# RF.net
KiCad netlist of a schematic drawn in Altium Designer
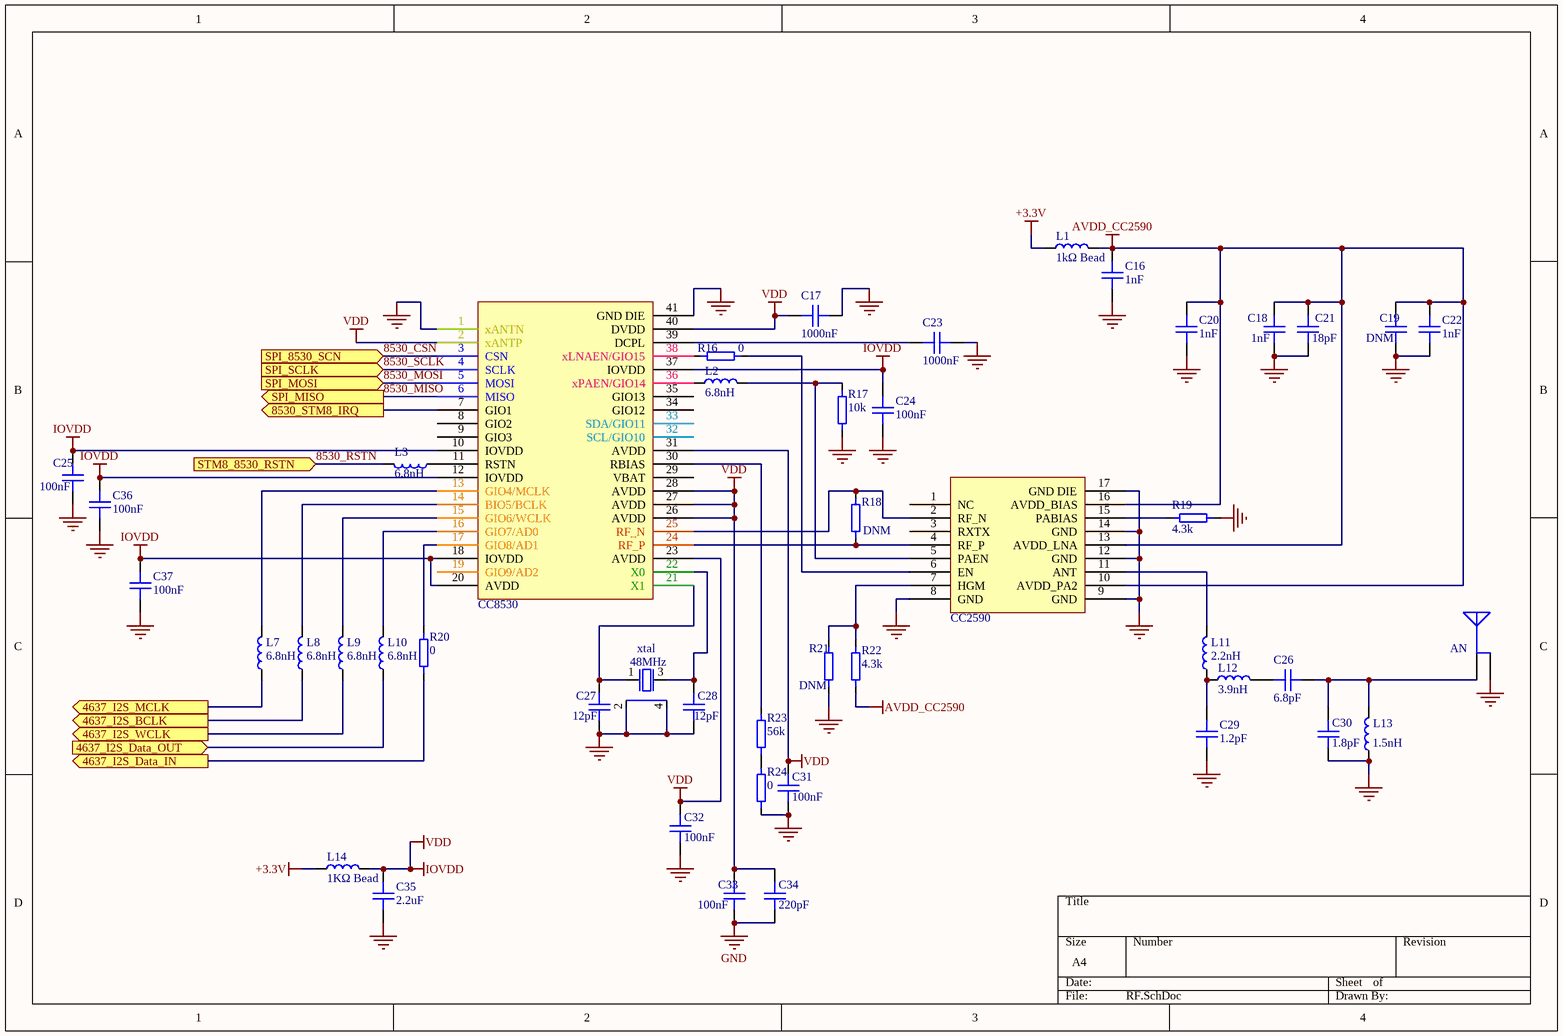
[diagram p0: RF.SchDoc]

(export (version "E")
  (design (tool "Eeschema 10.0.6"))
  (components
    (comp (ref "AN")
      (value "Antenna")
      (footprint "ANT_WIGGLE_1MM")
      (libsource (lib "SuperLib") (part "Antenna"))
    )
    (comp (ref "C16")
      (value "1nF")
      (footprint "SMD 0402")
      (fields (field (name "Comment") "Capacity SMD"))
      (libsource (lib "WPU161C") (part "Capacity SMD"))
    )
    (comp (ref "C17")
      (value "1000nF")
      (footprint "SMD 0402")
      (fields (field (name "Comment") "Capacity SMD"))
      (libsource (lib "WPU161C") (part "Capacity SMD"))
    )
    (comp (ref "C18")
      (value "1nF")
      (footprint "SMD 0402")
      (fields (field (name "Comment") "Capacity SMD"))
      (libsource (lib "WPU161C") (part "Capacity SMD"))
    )
    (comp (ref "C19")
      (value "DNM")
      (footprint "SMD 0402")
      (fields (field (name "Comment") "Capacity SMD"))
      (libsource (lib "WPU161C") (part "Capacity SMD"))
    )
    (comp (ref "C20")
      (value "1nF")
      (footprint "SMD 0402")
      (fields (field (name "Comment") "Capacity SMD"))
      (libsource (lib "WPU161C") (part "Capacity SMD"))
    )
    (comp (ref "C21")
      (value "18pF")
      (footprint "SMD 0402")
      (fields (field (name "Comment") "Capacity SMD"))
      (libsource (lib "WPU161C") (part "Capacity SMD"))
    )
    (comp (ref "C22")
      (value "1nF")
      (footprint "SMD 0402")
      (fields (field (name "Comment") "Capacity SMD"))
      (libsource (lib "WPU161C") (part "Capacity SMD"))
    )
    (comp (ref "C23")
      (value "1000nF")
      (footprint "SMD 0402")
      (fields (field (name "Comment") "Capacity SMD"))
      (libsource (lib "WPU161C") (part "Capacity SMD"))
    )
    (comp (ref "C24")
      (value "100nF")
      (footprint "SMD 0402")
      (fields (field (name "Comment") "Capacity SMD"))
      (libsource (lib "WPU161C") (part "Capacity SMD"))
    )
    (comp (ref "C25")
      (value "100nF")
      (footprint "SMD 0402")
      (fields (field (name "Comment") "Capacity SMD"))
      (libsource (lib "WPU161C") (part "Capacity SMD"))
    )
    (comp (ref "C26")
      (value "6.8pF")
      (footprint "SMD 0402")
      (fields (field (name "Comment") "Capacity SMD"))
      (libsource (lib "WPU161C") (part "Capacity SMD"))
    )
    (comp (ref "C27")
      (value "12pF")
      (footprint "SMD 0402")
      (fields (field (name "Comment") "Capacity SMD"))
      (libsource (lib "WPU161C") (part "Capacity SMD"))
    )
    (comp (ref "C28")
      (value "12pF")
      (footprint "SMD 0402")
      (fields (field (name "Comment") "Capacity SMD"))
      (libsource (lib "WPU161C") (part "Capacity SMD"))
    )
    (comp (ref "C29")
      (value "1.2pF")
      (footprint "SMD 0402")
      (fields (field (name "Comment") "Capacity SMD"))
      (libsource (lib "WPU161C") (part "Capacity SMD"))
    )
    (comp (ref "C30")
      (value "1.8pF")
      (footprint "SMD 0402")
      (fields (field (name "Comment") "Capacity SMD"))
      (libsource (lib "WPU161C") (part "Capacity SMD"))
    )
    (comp (ref "C31")
      (value "100nF")
      (footprint "SMD 0402")
      (fields (field (name "Comment") "Capacity SMD"))
      (libsource (lib "WPU161C") (part "Capacity SMD"))
    )
    (comp (ref "C32")
      (value "100nF")
      (footprint "SMD 0402")
      (fields (field (name "Comment") "Capacity SMD"))
      (libsource (lib "WPU161C") (part "Capacity SMD"))
    )
    (comp (ref "C33")
      (value "100nF")
      (footprint "SMD 0402")
      (fields (field (name "Comment") "Capacity SMD"))
      (libsource (lib "WPU161C") (part "Capacity SMD"))
    )
    (comp (ref "C34")
      (value "220pF")
      (footprint "SMD 0402")
      (fields (field (name "Comment") "Capacity SMD"))
      (libsource (lib "WPU161C") (part "Capacity SMD"))
    )
    (comp (ref "C35")
      (value "2.2uF")
      (footprint "SMD 0402")
      (fields (field (name "Comment") "Capacity SMD"))
      (libsource (lib "WPU161C") (part "Capacity SMD"))
    )
    (comp (ref "C36")
      (value "100nF")
      (footprint "SMD 0402")
      (fields (field (name "Comment") "Capacity SMD"))
      (libsource (lib "WPU161C") (part "Capacity SMD"))
    )
    (comp (ref "C37")
      (value "100nF")
      (footprint "SMD 0402")
      (fields (field (name "Comment") "Capacity SMD"))
      (libsource (lib "WPU161C") (part "Capacity SMD"))
    )
    (comp (ref "CC2590") (value "CC2590") (footprint "CC2590") (libsource (lib "WPU161C") (part "CC2590")))
    (comp (ref "CC8530") (value "CC8530") (footprint "CC8530") (libsource (lib "WPU161C") (part "CC8530")))
    (comp (ref "L1")
      (value "1kΩ Bead")
      (footprint "SMD 0402")
      (fields (field (name "Comment") "Inductor SMD"))
      (libsource (lib "WPU161C") (part "Inductor SMD"))
    )
    (comp (ref "L2")
      (value "6.8nH")
      (footprint "SMD 0402")
      (fields (field (name "Comment") "Inductor SMD"))
      (libsource (lib "WPU161C") (part "Inductor SMD"))
    )
    (comp (ref "L3")
      (value "6.8nH")
      (footprint "SMD 0402")
      (fields (field (name "Comment") "Inductor SMD"))
      (libsource (lib "WPU161C") (part "Inductor SMD"))
    )
    (comp (ref "L7")
      (value "6.8nH")
      (footprint "SMD 0402")
      (fields (field (name "Comment") "Inductor SMD"))
      (libsource (lib "WPU161C") (part "Inductor SMD"))
    )
    (comp (ref "L8")
      (value "6.8nH")
      (footprint "SMD 0402")
      (fields (field (name "Comment") "Inductor SMD"))
      (libsource (lib "WPU161C") (part "Inductor SMD"))
    )
    (comp (ref "L9")
      (value "6.8nH")
      (footprint "SMD 0402")
      (fields (field (name "Comment") "Inductor SMD"))
      (libsource (lib "WPU161C") (part "Inductor SMD"))
    )
    (comp (ref "L10")
      (value "6.8nH")
      (footprint "SMD 0402")
      (fields (field (name "Comment") "Inductor SMD"))
      (libsource (lib "WPU161C") (part "Inductor SMD"))
    )
    (comp (ref "L11")
      (value "2.2nH")
      (footprint "SMD 0402")
      (fields (field (name "Comment") "Inductor SMD"))
      (libsource (lib "WPU161C") (part "Inductor SMD"))
    )
    (comp (ref "L12")
      (value "3.9nH")
      (footprint "SMD 0402")
      (fields (field (name "Comment") "Inductor SMD"))
      (libsource (lib "WPU161C") (part "Inductor SMD"))
    )
    (comp (ref "L13")
      (value "1.5nH")
      (footprint "SMD 0402")
      (fields (field (name "Comment") "Inductor SMD"))
      (libsource (lib "WPU161C") (part "Inductor SMD"))
    )
    (comp (ref "L14")
      (value "1KΩ Bead")
      (footprint "SMD 0402")
      (fields (field (name "Comment") "Inductor SMD"))
      (libsource (lib "WPU161C") (part "Inductor SMD"))
    )
    (comp (ref "R16")
      (value "0")
      (footprint "SMD 0402")
      (fields (field (name "Comment") "Resistor SMD"))
      (libsource (lib "WPU161C") (part "Resistor SMD"))
    )
    (comp (ref "R17")
      (value "10k")
      (footprint "SMD 0402")
      (fields (field (name "Comment") "Resistor SMD"))
      (libsource (lib "WPU161C") (part "Resistor SMD"))
    )
    (comp (ref "R18")
      (value "DNM")
      (footprint "SMD 0402")
      (fields (field (name "Comment") "Resistor SMD"))
      (libsource (lib "WPU161C") (part "Resistor SMD"))
    )
    (comp (ref "R19")
      (value "4.3k")
      (footprint "SMD 0402")
      (fields (field (name "Comment") "Resistor SMD"))
      (libsource (lib "WPU161C") (part "Resistor SMD"))
    )
    (comp (ref "R20")
      (value "0")
      (footprint "SMD 0402")
      (fields (field (name "Comment") "Resistor SMD"))
      (libsource (lib "WPU161C") (part "Resistor SMD"))
    )
    (comp (ref "R21")
      (value "DNM")
      (footprint "SMD 0402")
      (fields (field (name "Comment") "Resistor SMD"))
      (libsource (lib "WPU161C") (part "Resistor SMD"))
    )
    (comp (ref "R22")
      (value "4.3k")
      (footprint "SMD 0402")
      (fields (field (name "Comment") "Resistor SMD"))
      (libsource (lib "WPU161C") (part "Resistor SMD"))
    )
    (comp (ref "R23")
      (value "56k")
      (footprint "SMD 0402")
      (fields (field (name "Comment") "Resistor SMD"))
      (libsource (lib "WPU161C") (part "Resistor SMD"))
    )
    (comp (ref "R24")
      (value "0")
      (footprint "SMD 0402")
      (fields (field (name "Comment") "Resistor SMD"))
      (libsource (lib "WPU161C") (part "Resistor SMD"))
    )
    (comp (ref "xtal")
      (value "48MHz")
      (footprint "xtal_3225_FA-128")
      (fields (field (name "PART NUMBER") "FA-128, 48.00000MHz") (field (name "Comment") "XTAL"))
      (libsource (lib "WPU161C") (part "XTAL"))
    )
  )
  (nets
    (net (code "1") (name "+3.3V") (class "Default")
      (node (ref "L1") (pin "1") (pintype "passive"))
      (node (ref "L14") (pin "1") (pintype "passive"))
    )
    (net (code "2") (name "/4637_I2S_BCLK") (class "Default") (node (ref "L8") (pin "1") (pintype "passive")))
    (net (code "3") (name "/4637_I2S_Data_IN") (class "Default")
      (node (ref "R20") (pin "1") (pintype "passive"))
    )
    (net (code "4") (name "/4637_I2S_Data_OUT") (class "Default")
      (node (ref "L10") (pin "1") (pintype "passive"))
    )
    (net (code "5") (name "/4637_I2S_MCLK") (class "Default") (node (ref "L7") (pin "1") (pintype "passive")))
    (net (code "6") (name "/4637_I2S_WCLK") (class "Default") (node (ref "L9") (pin "1") (pintype "passive")))
    (net (code "7") (name "/8530_CSN") (class "Default")
      (node (ref "CC8530") (pin "3") (pinfunction "CSN_3") (pintype "passive"))
    )
    (net (code "8") (name "/8530_MISO") (class "Default")
      (node (ref "CC8530") (pin "6") (pinfunction "MISO_6") (pintype "passive"))
    )
    (net (code "9") (name "/8530_MOSI") (class "Default")
      (node (ref "CC8530") (pin "5") (pinfunction "MOSI_5") (pintype "passive"))
    )
    (net (code "10") (name "/8530_RSTN") (class "Default") (node (ref "L3") (pin "2") (pintype "passive")))
    (net (code "11") (name "/8530_SCLK") (class "Default")
      (node (ref "CC8530") (pin "4") (pinfunction "SCLK_4") (pintype "passive"))
    )
    (net (code "12") (name "/8530_STM8_IRQ") (class "Default")
      (node (ref "CC8530") (pin "7") (pinfunction "GIO1_7") (pintype "passive"))
    )
    (net (code "13") (name "AVDD_CC2590") (class "Default")
      (node (ref "C16") (pin "2") (pintype "passive"))
      (node (ref "C18") (pin "2") (pintype "passive"))
      (node (ref "C19") (pin "2") (pintype "passive"))
      (node (ref "C20") (pin "2") (pintype "passive"))
      (node (ref "C21") (pin "2") (pintype "passive"))
      (node (ref "C22") (pin "2") (pintype "passive"))
      (node (ref "CC2590") (pin "10") (pinfunction "AVDD_PA2_10") (pintype "passive"))
      (node (ref "CC2590") (pin "13") (pinfunction "AVDD_LNA_13") (pintype "passive"))
      (node (ref "CC2590") (pin "16") (pinfunction "AVDD_BIAS_16") (pintype "passive"))
      (node (ref "L1") (pin "2") (pintype "passive"))
      (node (ref "R22") (pin "1") (pintype "passive"))
    )
    (net (code "14") (name "GND") (class "Default")
      (node (ref "AN") (pin "2") (pintype "passive"))
      (node (ref "C16") (pin "1") (pintype "passive"))
      (node (ref "C17") (pin "2") (pintype "passive"))
      (node (ref "C18") (pin "1") (pintype "passive"))
      (node (ref "C19") (pin "1") (pintype "passive"))
      (node (ref "C20") (pin "1") (pintype "passive"))
      (node (ref "C21") (pin "1") (pintype "passive"))
      (node (ref "C22") (pin "1") (pintype "passive"))
      (node (ref "C23") (pin "2") (pintype "passive"))
      (node (ref "C24") (pin "1") (pintype "passive"))
      (node (ref "C25") (pin "1") (pintype "passive"))
      (node (ref "C27") (pin "1") (pintype "passive"))
      (node (ref "C28") (pin "1") (pintype "passive"))
      (node (ref "C29") (pin "1") (pintype "passive"))
      (node (ref "C30") (pin "1") (pintype "passive"))
      (node (ref "C31") (pin "1") (pintype "passive"))
      (node (ref "C32") (pin "1") (pintype "passive"))
      (node (ref "C33") (pin "1") (pintype "passive"))
      (node (ref "C34") (pin "1") (pintype "passive"))
      (node (ref "C35") (pin "1") (pintype "passive"))
      (node (ref "C36") (pin "1") (pintype "passive"))
      (node (ref "C37") (pin "1") (pintype "passive"))
      (node (ref "CC2590") (pin "12") (pinfunction "GND_12") (pintype "passive"))
      (node (ref "CC2590") (pin "14") (pinfunction "GND_14") (pintype "passive"))
      (node (ref "CC2590") (pin "17") (pinfunction "GND_DIE_17") (pintype "passive"))
      (node (ref "CC2590") (pin "8") (pinfunction "GND_8") (pintype "passive"))
      (node (ref "CC2590") (pin "9") (pinfunction "GND_9") (pintype "passive"))
      (node (ref "CC8530") (pin "1") (pinfunction "xANTN_1") (pintype "passive"))
      (node (ref "CC8530") (pin "41") (pinfunction "GND_DIE_41") (pintype "passive"))
      (node (ref "L13") (pin "1") (pintype "passive"))
      (node (ref "R17") (pin "1") (pintype "passive"))
      (node (ref "R19") (pin "2") (pintype "passive"))
      (node (ref "R21") (pin "1") (pintype "passive"))
      (node (ref "R24") (pin "1") (pintype "passive"))
      (node (ref "xtal") (pin "2") (pinfunction "2_2") (pintype "passive"))
      (node (ref "xtal") (pin "4") (pinfunction "4_4") (pintype "passive"))
    )
    (net (code "15") (name "IOVDD") (class "Default")
      (node (ref "C17") (pin "1") (pintype "passive"))
      (node (ref "C24") (pin "2") (pintype "passive"))
      (node (ref "C25") (pin "2") (pintype "passive"))
      (node (ref "C31") (pin "2") (pintype "passive"))
      (node (ref "C32") (pin "2") (pintype "passive"))
      (node (ref "C33") (pin "2") (pintype "passive"))
      (node (ref "C34") (pin "2") (pintype "passive"))
      (node (ref "C35") (pin "2") (pintype "passive"))
      (node (ref "C36") (pin "2") (pintype "passive"))
      (node (ref "C37") (pin "2") (pintype "passive"))
      (node (ref "CC8530") (pin "10") (pinfunction "IOVDD_10") (pintype "passive"))
      (node (ref "CC8530") (pin "12") (pinfunction "IOVDD_12") (pintype "passive"))
      (node (ref "CC8530") (pin "18") (pinfunction "IOVDD_18") (pintype "passive"))
      (node (ref "CC8530") (pin "2") (pinfunction "xANTP_2") (pintype "passive"))
      (node (ref "CC8530") (pin "20") (pinfunction "AVDD_20") (pintype "passive"))
      (node (ref "CC8530") (pin "23") (pinfunction "AVDD_23") (pintype "passive"))
      (node (ref "CC8530") (pin "26") (pinfunction "AVDD_26") (pintype "passive"))
      (node (ref "CC8530") (pin "27") (pinfunction "AVDD_27") (pintype "passive"))
      (node (ref "CC8530") (pin "28") (pinfunction "AVDD_28") (pintype "passive"))
      (node (ref "CC8530") (pin "31") (pinfunction "AVDD_31") (pintype "passive"))
      (node (ref "CC8530") (pin "37") (pinfunction "IOVDD_37") (pintype "passive"))
      (node (ref "CC8530") (pin "40") (pinfunction "DVDD_40") (pintype "passive"))
      (node (ref "L14") (pin "2") (pintype "passive"))
    )
    (net (code "16") (name "Net-(AN-Pad1)") (class "Default")
      (node (ref "AN") (pin "1") (pintype "passive"))
      (node (ref "C26") (pin "2") (pintype "passive"))
      (node (ref "C30") (pin "2") (pintype "passive"))
      (node (ref "L13") (pin "2") (pintype "passive"))
    )
    (net (code "17") (name "Net-(C26-Pad1)") (class "Default")
      (node (ref "C26") (pin "1") (pintype "passive"))
      (node (ref "L12") (pin "2") (pintype "passive"))
    )
    (net (code "18") (name "Net-(C29-Pad2)") (class "Default")
      (node (ref "C29") (pin "2") (pintype "passive"))
      (node (ref "L11") (pin "1") (pintype "passive"))
      (node (ref "L12") (pin "1") (pintype "passive"))
    )
    (net (code "19") (name "Net-(CC2590-ANT)") (class "Default")
      (node (ref "CC2590") (pin "11") (pinfunction "ANT_11") (pintype "passive"))
      (node (ref "L11") (pin "2") (pintype "passive"))
    )
    (net (code "20") (name "Net-(CC2590-EN)") (class "Default")
      (node (ref "CC2590") (pin "6") (pinfunction "EN_6") (pintype "passive"))
      (node (ref "R16") (pin "2") (pintype "passive"))
    )
    (net (code "21") (name "Net-(CC2590-HGM)") (class "Default")
      (node (ref "CC2590") (pin "7") (pinfunction "HGM_7") (pintype "passive"))
      (node (ref "R21") (pin "2") (pintype "passive"))
      (node (ref "R22") (pin "2") (pintype "passive"))
    )
    (net (code "22") (name "Net-(CC2590-PABIAS)") (class "Default")
      (node (ref "CC2590") (pin "15") (pinfunction "PABIAS_15") (pintype "passive"))
      (node (ref "R19") (pin "1") (pintype "passive"))
    )
    (net (code "23") (name "Net-(CC2590-PAEN)") (class "Default")
      (node (ref "CC2590") (pin "5") (pinfunction "PAEN_5") (pintype "passive"))
      (node (ref "L2") (pin "2") (pintype "passive"))
      (node (ref "R17") (pin "2") (pintype "passive"))
    )
    (net (code "24") (name "Net-(CC2590-RF_N)") (class "Default")
      (node (ref "CC2590") (pin "2") (pinfunction "RF_N_2") (pintype "passive"))
      (node (ref "CC8530") (pin "25") (pinfunction "RF_N_25") (pintype "passive"))
      (node (ref "R18") (pin "2") (pintype "passive"))
    )
    (net (code "25") (name "Net-(CC2590-RF_P)") (class "Default")
      (node (ref "CC2590") (pin "4") (pinfunction "RF_P_4") (pintype "passive"))
      (node (ref "CC8530") (pin "24") (pinfunction "RF_P_24") (pintype "passive"))
      (node (ref "R18") (pin "1") (pintype "passive"))
    )
    (net (code "26") (name "Net-(CC8530-BIO5{slash}BCLK)") (class "Default")
      (node (ref "CC8530") (pin "14") (pinfunction "BIO5/BCLK_14") (pintype "passive"))
      (node (ref "L8") (pin "2") (pintype "passive"))
    )
    (net (code "27") (name "Net-(CC8530-DCPL)") (class "Default")
      (node (ref "C23") (pin "1") (pintype "passive"))
      (node (ref "CC8530") (pin "39") (pinfunction "DCPL_39") (pintype "passive"))
    )
    (net (code "28") (name "Net-(CC8530-GIO4{slash}MCLK)") (class "Default")
      (node (ref "CC8530") (pin "13") (pinfunction "GIO4/MCLK_13") (pintype "passive"))
      (node (ref "L7") (pin "2") (pintype "passive"))
    )
    (net (code "29") (name "Net-(CC8530-GIO6{slash}WCLK)") (class "Default")
      (node (ref "CC8530") (pin "15") (pinfunction "GIO6/WCLK_15") (pintype "passive"))
      (node (ref "L9") (pin "2") (pintype "passive"))
    )
    (net (code "30") (name "Net-(CC8530-GIO7{slash}AD0)") (class "Default")
      (node (ref "CC8530") (pin "16") (pinfunction "GIO7/AD0_16") (pintype "passive"))
      (node (ref "L10") (pin "2") (pintype "passive"))
    )
    (net (code "31") (name "Net-(CC8530-GIO8{slash}AD1)") (class "Default")
      (node (ref "CC8530") (pin "17") (pinfunction "GIO8/AD1_17") (pintype "passive"))
      (node (ref "R20") (pin "2") (pintype "passive"))
    )
    (net (code "32") (name "Net-(CC8530-RBIAS)") (class "Default")
      (node (ref "CC8530") (pin "30") (pinfunction "RBIAS_30") (pintype "passive"))
      (node (ref "R23") (pin "2") (pintype "passive"))
    )
    (net (code "33") (name "Net-(CC8530-RSTN)") (class "Default")
      (node (ref "CC8530") (pin "11") (pinfunction "RSTN_11") (pintype "passive"))
      (node (ref "L3") (pin "1") (pintype "passive"))
    )
    (net (code "34") (name "Net-(CC8530-X0)") (class "Default")
      (node (ref "C28") (pin "2") (pintype "passive"))
      (node (ref "CC8530") (pin "22") (pinfunction "X0_22") (pintype "passive"))
      (node (ref "xtal") (pin "3") (pinfunction "out_3") (pintype "passive"))
    )
    (net (code "35") (name "Net-(CC8530-X1)") (class "Default")
      (node (ref "C27") (pin "2") (pintype "passive"))
      (node (ref "CC8530") (pin "21") (pinfunction "X1_21") (pintype "passive"))
      (node (ref "xtal") (pin "1") (pinfunction "inp_1") (pintype "passive"))
    )
    (net (code "36") (name "Net-(CC8530-xLNAEN{slash}GIO15)") (class "Default")
      (node (ref "CC8530") (pin "38") (pinfunction "xLNAEN/GIO15_38") (pintype "passive"))
      (node (ref "R16") (pin "1") (pintype "passive"))
    )
    (net (code "37") (name "Net-(CC8530-xPAEN{slash}GIO14)") (class "Default")
      (node (ref "CC8530") (pin "36") (pinfunction "xPAEN/GIO14_36") (pintype "passive"))
      (node (ref "L2") (pin "1") (pintype "passive"))
    )
    (net (code "38") (name "Net-(R23-Pad1)") (class "Default")
      (node (ref "R23") (pin "1") (pintype "passive"))
      (node (ref "R24") (pin "2") (pintype "passive"))
    )
    (net (code "39") (name "unconnected-(CC2590-NC-Pad1)") (class "Default")
      (node (ref "CC2590") (pin "1") (pinfunction "NC_1") (pintype "passive"))
    )
    (net (code "40") (name "unconnected-(CC2590-RXTX-Pad3)") (class "Default")
      (node (ref "CC2590") (pin "3") (pinfunction "RXTX_3") (pintype "passive"))
    )
    (net (code "41") (name "unconnected-(CC8530-GIO2-Pad8)") (class "Default")
      (node (ref "CC8530") (pin "8") (pinfunction "GIO2_8") (pintype "passive"))
    )
    (net (code "42") (name "unconnected-(CC8530-GIO3-Pad9)") (class "Default")
      (node (ref "CC8530") (pin "9") (pinfunction "GIO3_9") (pintype "passive"))
    )
    (net (code "43") (name "unconnected-(CC8530-GIO9{slash}AD2-Pad19)") (class "Default")
      (node (ref "CC8530") (pin "19") (pinfunction "GIO9/AD2_19") (pintype "passive"))
    )
    (net (code "44") (name "unconnected-(CC8530-GIO12-Pad34)") (class "Default")
      (node (ref "CC8530") (pin "34") (pinfunction "GIO12_34") (pintype "passive"))
    )
    (net (code "45") (name "unconnected-(CC8530-GIO13-Pad35)") (class "Default")
      (node (ref "CC8530") (pin "35") (pinfunction "GIO13_35") (pintype "passive"))
    )
    (net (code "46") (name "unconnected-(CC8530-SCL{slash}GIO10-Pad32)") (class "Default")
      (node (ref "CC8530") (pin "32") (pinfunction "SCL/GIO10_32") (pintype "passive"))
    )
    (net (code "47") (name "unconnected-(CC8530-SDA{slash}GIO11-Pad33)") (class "Default")
      (node (ref "CC8530") (pin "33") (pinfunction "SDA/GIO11_33") (pintype "passive"))
    )
    (net (code "48") (name "unconnected-(CC8530-VBAT-Pad29)") (class "Default")
      (node (ref "CC8530") (pin "29") (pinfunction "VBAT_29") (pintype "passive"))
    )
    (net (code "49") (name "unconnected-(xtal-GND-Pad2)") (class "Default")
      (node (ref "xtal") (pin "2") (pinfunction "GND_2") (pintype "passive"))
    )
    (net (code "50") (name "unconnected-(xtal-GND-Pad4)") (class "Default")
      (node (ref "xtal") (pin "4") (pinfunction "GND_4") (pintype "passive"))
    )
  )
)
